# s0-interface.net
KiCad netlist of a schematic drawn in EAGLE
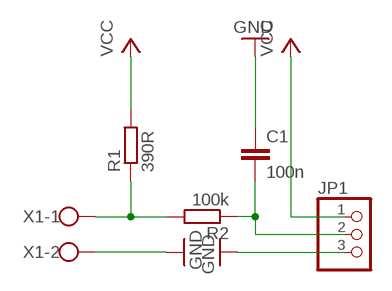
[diagram p0: schematic, sheet 1]

(export (version "E")
  (design (tool "Eeschema 10.0.6"))
  (components
    (comp (ref "C1")
      (value "100n")
      (footprint "eagle-import:C0603")
      (libsource (lib "eagle-import") (part "C-EUC0603"))
    )
    (comp (ref "JP1")
      (value "PINHD-1X3")
      (footprint "eagle-import:1X03")
      (libsource (lib "eagle-import") (part "PINHD-1X3"))
    )
    (comp (ref "R1")
      (value "390R")
      (footprint "eagle-import:R0603")
      (libsource (lib "eagle-import") (part "R-EU_R0603"))
    )
    (comp (ref "R2")
      (value "100k")
      (footprint "eagle-import:R0603")
      (libsource (lib "eagle-import") (part "R-EU_R0603"))
    )
    (comp (ref "X1")
      (value "W237-102")
      (footprint "eagle-import:W237-102")
      (fields (field (name "MPN") "237-102"))
      (libsource (lib "eagle-import") (part "W237-102"))
    )
  )
  (nets
    (net (code "1") (name "GND") (class "Default")
      (node (ref "C1") (pin "1") (pinfunction "1_1") (pintype "passive"))
      (node (ref "JP1") (pin "3") (pinfunction "3_3") (pintype "passive"))
      (node (ref "X1") (pin "2") (pinfunction "KL_2") (pintype "passive"))
    )
    (net (code "2") (name "Net-(C1-Pad2)") (class "Default")
      (node (ref "C1") (pin "2") (pinfunction "2_2") (pintype "passive"))
      (node (ref "JP1") (pin "2") (pinfunction "2_2") (pintype "passive"))
      (node (ref "R2") (pin "1") (pinfunction "1_1") (pintype "passive"))
    )
    (net (code "3") (name "Net-(X1A-KL)") (class "Default")
      (node (ref "R1") (pin "1") (pinfunction "1_1") (pintype "passive"))
      (node (ref "R2") (pin "2") (pinfunction "2_2") (pintype "passive"))
      (node (ref "X1") (pin "1") (pinfunction "KL_1") (pintype "passive"))
    )
    (net (code "4") (name "VCC") (class "Default")
      (node (ref "JP1") (pin "1") (pinfunction "1_1") (pintype "passive"))
      (node (ref "R1") (pin "2") (pinfunction "2_2") (pintype "passive"))
    )
  )
)
